# ProPrj__pcb__2024-10-03.net
KiCad netlist of a schematic drawn in EasyEDA Pro
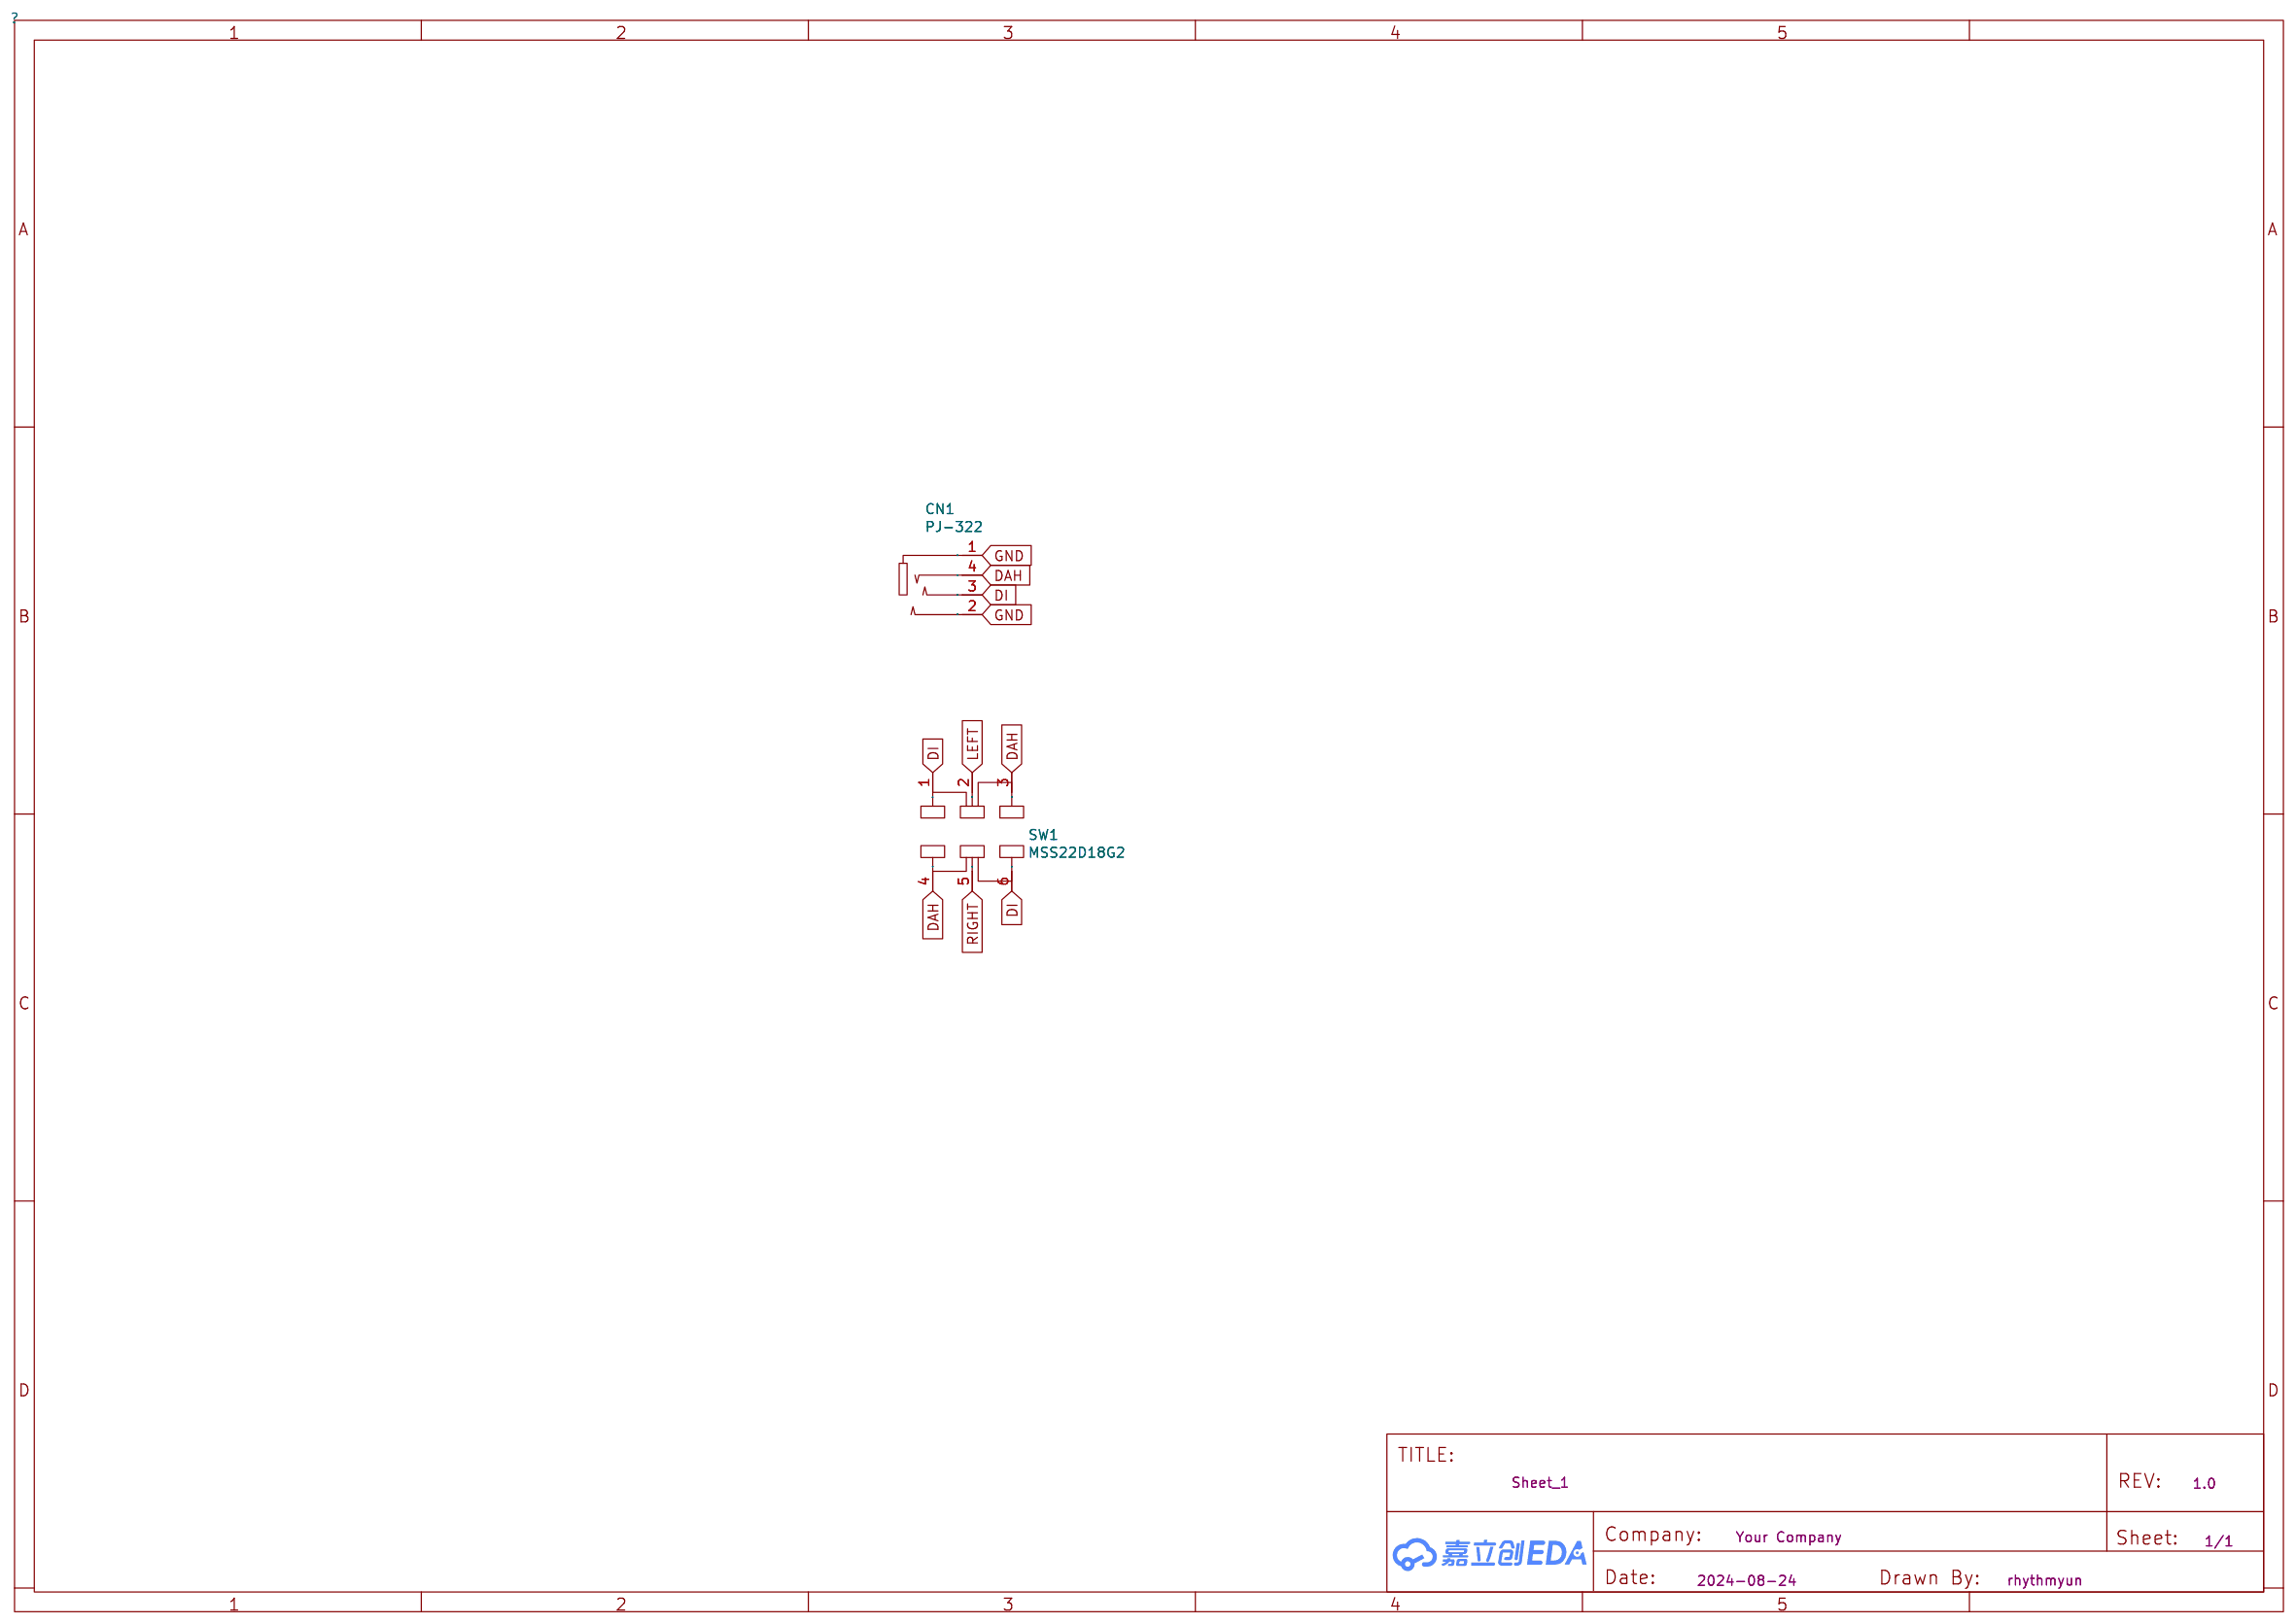
[diagram p0: schematic sheet]

(export (version "E")
  (design (tool "Eeschema 10.0.6"))
  (components
    (comp (ref "CN1")
      (value "PJ-322")
      (footprint "easyedapro:AUDIO-TH_HOOYA_PJ-322")
      (fields (field (name "Manufacturer Part") "PJ-322环保") (field (name "Manufacturer") "HOOYA(皓宇电子)"))
      (libsource (lib "easyedapro") (part "PJ-322"))
    )
    (comp (ref "SW1")
      (value "MSS22D18G2")
      (footprint "easyedapro:SW-TH_MSS22D18GX")
      (fields (field (name "Manufacturer") "SHOU HAN(首韩)"))
      (libsource (lib "easyedapro") (part "MSS22D18G2"))
    )
  )
  (nets
    (net (code "1") (name "DAH") (class "Default")
      (node (ref "CN1") (pin "4") (pinfunction "4_4") (pintype "unspecified"))
      (node (ref "SW1") (pin "3") (pinfunction "3_3") (pintype "unspecified"))
      (node (ref "SW1") (pin "4") (pinfunction "4_4") (pintype "unspecified"))
    )
    (net (code "2") (name "DI") (class "Default")
      (node (ref "CN1") (pin "3") (pinfunction "3_3") (pintype "unspecified"))
      (node (ref "SW1") (pin "1") (pinfunction "1_1") (pintype "unspecified"))
      (node (ref "SW1") (pin "6") (pinfunction "6_6") (pintype "unspecified"))
    )
    (net (code "3") (name "GND") (class "Default")
      (node (ref "CN1") (pin "1") (pinfunction "1_1") (pintype "unspecified"))
      (node (ref "CN1") (pin "2") (pinfunction "2_2") (pintype "unspecified"))
    )
    (net (code "4") (name "LEFT") (class "Default")
      (node (ref "SW1") (pin "2") (pinfunction "2_2") (pintype "unspecified"))
    )
    (net (code "5") (name "RIGHT") (class "Default")
      (node (ref "SW1") (pin "5") (pinfunction "5_5") (pintype "unspecified"))
    )
  )
)
